# ASM2001.net
KiCad netlist of a schematic drawn in EAGLE
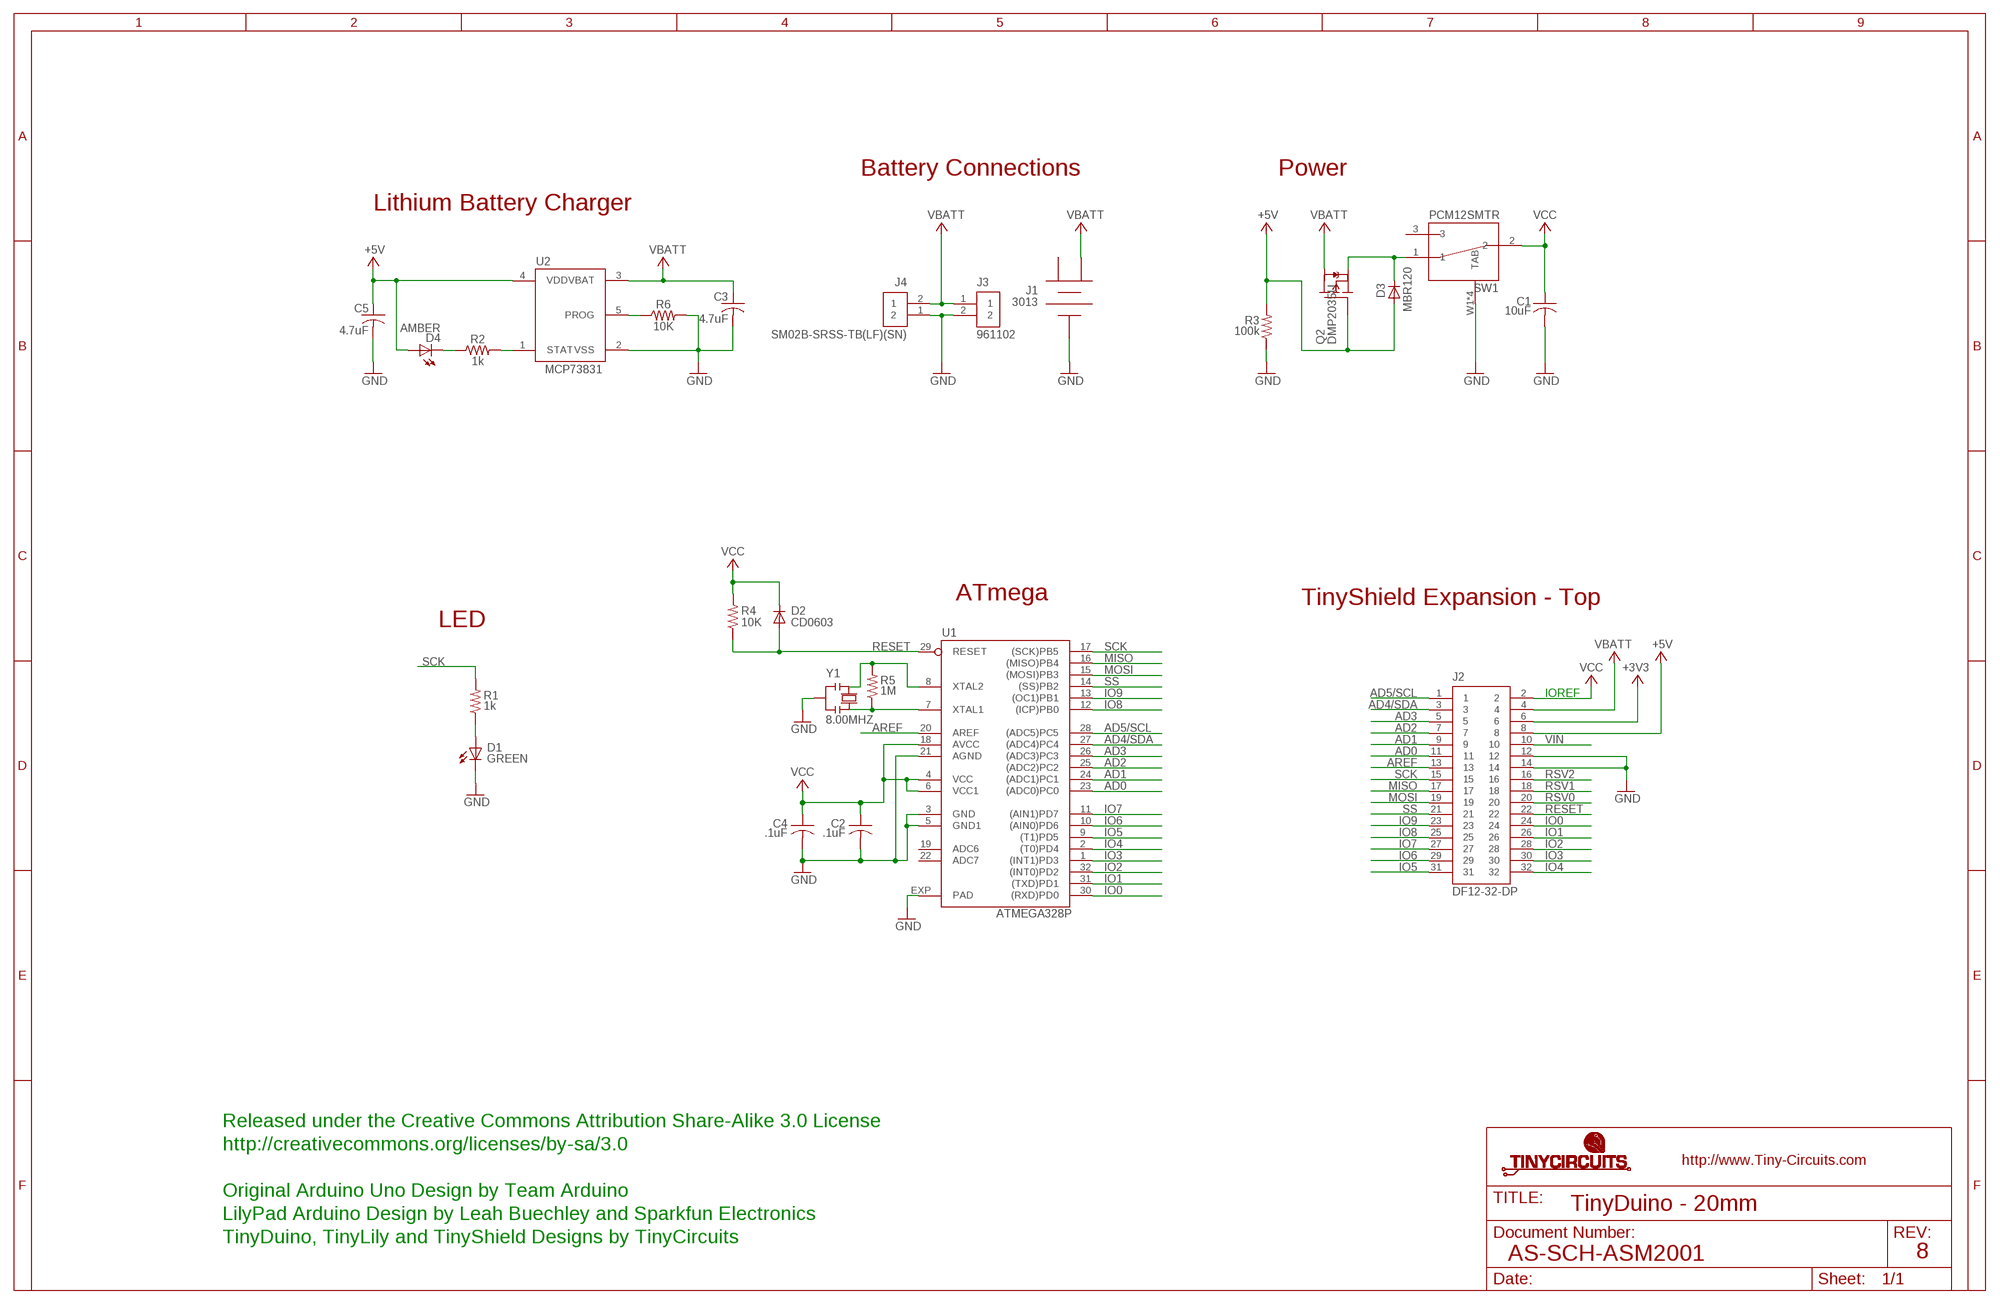
[diagram p0: schematic, sheet 1]

(export (version "E")
  (design (tool "Eeschema 10.0.6"))
  (components
    (comp (ref "C1")
      (value "10uF")
      (footprint "eagle-import:C0603")
      (fields (field (name "PARTNO") "AS-ITM-00002") (field (name "PARTNO_1") "AS-ITM-00002"))
      (libsource (lib "eagle-import") (part "AS-ITM-00002"))
    )
    (comp (ref "C2")
      (value ".1uF")
      (footprint "eagle-import:C0402")
      (fields (field (name "PARTNO") "AS-ITM-00008") (field (name "PARTNO_1") "AS-ITM-00008"))
      (libsource (lib "eagle-import") (part "AS-ITM-00008"))
    )
    (comp (ref "C3")
      (value "4.7uF")
      (footprint "eagle-import:C0402")
      (fields (field (name "PARTNO") "AS-ITM-00242") (field (name "PARTNO_1") "AS-ITM-00242"))
      (libsource (lib "eagle-import") (part "AS-ITM-00242"))
    )
    (comp (ref "C4")
      (value ".1uF")
      (footprint "eagle-import:C0402")
      (fields (field (name "PARTNO") "AS-ITM-00008") (field (name "PARTNO_1") "AS-ITM-00008"))
      (libsource (lib "eagle-import") (part "AS-ITM-00008"))
    )
    (comp (ref "C5")
      (value "4.7uF")
      (footprint "eagle-import:C0402")
      (fields (field (name "PARTNO") "AS-ITM-00242") (field (name "PARTNO_1") "AS-ITM-00242"))
      (libsource (lib "eagle-import") (part "AS-ITM-00242"))
    )
    (comp (ref "D1")
      (value "GREEN")
      (footprint "eagle-import:LNJ_LED")
      (fields (field (name "PARTNO") "AS-ITM-00011") (field (name "PARTNO_1") "AS-ITM-00011"))
      (libsource (lib "eagle-import") (part "AS-ITM-00011"))
    )
    (comp (ref "D2")
      (value "CD0603")
      (footprint "eagle-import:0603")
      (fields (field (name "PARTNO") "AS-ITM-00009") (field (name "PARTNO_1") "AS-ITM-00009"))
      (libsource (lib "eagle-import") (part "AS-ITM-00009"))
    )
    (comp (ref "D3")
      (value "MBR120")
      (footprint "eagle-import:SOD-123FL")
      (fields (field (name "PARTNO") "AS-ITM-00111"))
      (libsource (lib "eagle-import") (part "AS-ITM-00111"))
    )
    (comp (ref "D4")
      (value "AMBER")
      (footprint "eagle-import:LNJ_LED")
      (fields (field (name "PARTNO") "AS-ITM-00026") (field (name "PARTNO_1") "AS-ITM-00026"))
      (libsource (lib "eagle-import") (part "AS-ITM-00026"))
    )
    (comp (ref "J1")
      (value "3013")
      (footprint "eagle-import:3013")
      (fields (field (name "PARTNO") "AS-ITM-00001") (field (name "PARTNO_1") "AS-ITM-00001"))
      (libsource (lib "eagle-import") (part "AS-ITM-00001"))
    )
    (comp (ref "J2")
      (value "DF12-32-DP")
      (footprint "eagle-import:DF12-32-DP")
      (fields (field (name "PARTNO") "AS-ITM-00015") (field (name "PARTNO_1") "AS-ITM-00015"))
      (libsource (lib "eagle-import") (part "AS-ITM-00015"))
    )
    (comp (ref "J3")
      (value "961102")
      (footprint "eagle-import:2X.1_")
      (fields (field (name "PARTNO") "AS-ITM-00044"))
      (libsource (lib "eagle-import") (part "AS-ITM-00044"))
    )
    (comp (ref "J4")
      (value "SM02B-SRSS-TB(LF)(SN)")
      (footprint "eagle-import:JST_SH_2X1")
      (fields (field (name "PARTNO") "AS-ITM-00231"))
      (libsource (lib "eagle-import") (part "AS-ITM-00231"))
    )
    (comp (ref "Q2")
      (value "DMP2035U")
      (footprint "eagle-import:SOT23")
      (fields (field (name "PARTNO") "AS-ITM-00024"))
      (libsource (lib "eagle-import") (part "AS-ITM-00024"))
    )
    (comp (ref "R1")
      (value "1k")
      (footprint "eagle-import:0402")
      (fields (field (name "PARTNO") "AS-ITM-00003") (field (name "PARTNO_1") "AS-ITM-00003"))
      (libsource (lib "eagle-import") (part "AS-ITM-00003"))
    )
    (comp (ref "R2")
      (value "1k")
      (footprint "eagle-import:0402")
      (fields (field (name "PARTNO") "AS-ITM-00003") (field (name "PARTNO_1") "AS-ITM-00003"))
      (libsource (lib "eagle-import") (part "AS-ITM-00003"))
    )
    (comp (ref "R3")
      (value "100k")
      (footprint "eagle-import:0402")
      (fields (field (name "PARTNO") "AS-ITM-00004") (field (name "PARTNO_1") "AS-ITM-00004"))
      (libsource (lib "eagle-import") (part "AS-ITM-00004"))
    )
    (comp (ref "R4")
      (value "10K")
      (footprint "eagle-import:0402")
      (fields (field (name "PARTNO") "AS-ITM-00032") (field (name "PARTNO_1") "AS-ITM-00032"))
      (libsource (lib "eagle-import") (part "AS-ITM-00032"))
    )
    (comp (ref "R5")
      (value "1M")
      (footprint "eagle-import:0402")
      (fields (field (name "PARTNO") "AS-ITM-00005") (field (name "PARTNO_1") "AS-ITM-00005"))
      (libsource (lib "eagle-import") (part "AS-ITM-00005"))
    )
    (comp (ref "R6")
      (value "10K")
      (footprint "eagle-import:0402")
      (fields (field (name "PARTNO") "AS-ITM-00032"))
      (libsource (lib "eagle-import") (part "AS-ITM-00032"))
    )
    (comp (ref "SW1")
      (value "PCM12SMTR")
      (footprint "eagle-import:PCM12SMTR")
      (fields (field (name "PARTNO") "AS-ITM-00220"))
      (libsource (lib "eagle-import") (part "AS-ITM-00220"))
    )
    (comp (ref "U1")
      (value "ATMEGA328P")
      (footprint "eagle-import:ATMEL_QFN32")
      (fields (field (name "PARTNO") "AS-ITM-00013") (field (name "PARTNO_1") "AS-ITM-00013"))
      (libsource (lib "eagle-import") (part "AS-ITM-00013MU"))
    )
    (comp (ref "U2")
      (value "MCP73831")
      (footprint "eagle-import:SOT-23")
      (fields (field (name "PARTNO") "AS-ITM-00136"))
      (libsource (lib "eagle-import") (part "AS-ITM-00136"))
    )
    (comp (ref "Y1")
      (value "8.00MHZ")
      (footprint "eagle-import:RESONATOR_SMALL")
      (fields (field (name "PARTNO") "AS-ITM-0027") (field (name "PARTNO_1") "AS-ITM-00027"))
      (libsource (lib "eagle-import") (part "AS-ITM-00027B"))
    )
  )
  (nets
    (net (code "1") (name "+3V3") (class "Default")
      (node (ref "J2") (pin "6") (pinfunction "6_6") (pintype "bidirectional"))
    )
    (net (code "2") (name "+5V") (class "Default")
      (node (ref "C5") (pin "1") (pinfunction "1_1") (pintype "passive"))
      (node (ref "D3") (pin "A") (pinfunction "A_A") (pintype "passive"))
      (node (ref "D4") (pin "A") (pinfunction "A_A") (pintype "passive"))
      (node (ref "J2") (pin "8") (pinfunction "8_8") (pintype "bidirectional"))
      (node (ref "Q2") (pin "B") (pinfunction "G_B") (pintype "passive"))
      (node (ref "R3") (pin "2") (pinfunction "2_2") (pintype "passive"))
      (node (ref "U2") (pin "4") (pinfunction "VDD_4") (pintype "bidirectional"))
    )
    (net (code "3") (name "/1") (class "Default")
      (node (ref "J1") (pin "1") (pinfunction "1_1") (pintype "power_in"))
    )
    (net (code "4") (name "/AD0") (class "Default")
      (node (ref "J2") (pin "11") (pinfunction "11_11") (pintype "bidirectional"))
      (node (ref "U1") (pin "23") (pinfunction "(ADC0)PC0_23") (pintype "bidirectional"))
    )
    (net (code "5") (name "/AD1") (class "Default")
      (node (ref "J2") (pin "9") (pinfunction "9_9") (pintype "bidirectional"))
      (node (ref "U1") (pin "24") (pinfunction "(ADC1)PC1_24") (pintype "bidirectional"))
    )
    (net (code "6") (name "/AD2") (class "Default")
      (node (ref "J2") (pin "7") (pinfunction "7_7") (pintype "bidirectional"))
      (node (ref "U1") (pin "25") (pinfunction "(ADC2)PC2_25") (pintype "bidirectional"))
    )
    (net (code "7") (name "/AD3") (class "Default")
      (node (ref "J2") (pin "5") (pinfunction "5_5") (pintype "bidirectional"))
      (node (ref "U1") (pin "26") (pinfunction "(ADC3)PC3_26") (pintype "bidirectional"))
    )
    (net (code "8") (name "/AD4{slash}SDA") (class "Default")
      (node (ref "J2") (pin "3") (pinfunction "3_3") (pintype "bidirectional"))
      (node (ref "U1") (pin "27") (pinfunction "(ADC4)PC4_27") (pintype "bidirectional"))
    )
    (net (code "9") (name "/AD5{slash}SCL") (class "Default")
      (node (ref "J2") (pin "1") (pinfunction "1_1") (pintype "bidirectional"))
      (node (ref "U1") (pin "28") (pinfunction "(ADC5)PC5_28") (pintype "bidirectional"))
    )
    (net (code "10") (name "/AREF") (class "Default")
      (node (ref "J2") (pin "13") (pinfunction "13_13") (pintype "bidirectional"))
      (node (ref "U1") (pin "20") (pinfunction "AREF_20") (pintype "passive"))
    )
    (net (code "11") (name "/IO0") (class "Default")
      (node (ref "J2") (pin "24") (pinfunction "24_24") (pintype "bidirectional"))
      (node (ref "U1") (pin "30") (pinfunction "(RXD)PD0_30") (pintype "bidirectional"))
    )
    (net (code "12") (name "/IO1") (class "Default")
      (node (ref "J2") (pin "26") (pinfunction "26_26") (pintype "bidirectional"))
      (node (ref "U1") (pin "31") (pinfunction "(TXD)PD1_31") (pintype "bidirectional"))
    )
    (net (code "13") (name "/IO2") (class "Default")
      (node (ref "J2") (pin "28") (pinfunction "28_28") (pintype "bidirectional"))
      (node (ref "U1") (pin "32") (pinfunction "(INT0)PD2_32") (pintype "bidirectional"))
    )
    (net (code "14") (name "/IO3") (class "Default")
      (node (ref "J2") (pin "30") (pinfunction "30_30") (pintype "bidirectional"))
      (node (ref "U1") (pin "1") (pinfunction "(INT1)PD3_1") (pintype "bidirectional"))
    )
    (net (code "15") (name "/IO4") (class "Default")
      (node (ref "J2") (pin "32") (pinfunction "32_32") (pintype "bidirectional"))
      (node (ref "U1") (pin "2") (pinfunction "(T0)PD4_2") (pintype "bidirectional"))
    )
    (net (code "16") (name "/IO5") (class "Default")
      (node (ref "J2") (pin "31") (pinfunction "31_31") (pintype "bidirectional"))
      (node (ref "U1") (pin "9") (pinfunction "(T1)PD5_9") (pintype "bidirectional"))
    )
    (net (code "17") (name "/IO6") (class "Default")
      (node (ref "J2") (pin "29") (pinfunction "29_29") (pintype "bidirectional"))
      (node (ref "U1") (pin "10") (pinfunction "(AIN0)PD6_10") (pintype "bidirectional"))
    )
    (net (code "18") (name "/IO7") (class "Default")
      (node (ref "J2") (pin "27") (pinfunction "27_27") (pintype "bidirectional"))
      (node (ref "U1") (pin "11") (pinfunction "(AIN1)PD7_11") (pintype "bidirectional"))
    )
    (net (code "19") (name "/IO8") (class "Default")
      (node (ref "J2") (pin "25") (pinfunction "25_25") (pintype "bidirectional"))
      (node (ref "U1") (pin "12") (pinfunction "(ICP)PB0_12") (pintype "bidirectional"))
    )
    (net (code "20") (name "/IO9") (class "Default")
      (node (ref "J2") (pin "23") (pinfunction "23_23") (pintype "bidirectional"))
      (node (ref "U1") (pin "13") (pinfunction "(OC1)PB1_13") (pintype "bidirectional"))
    )
    (net (code "21") (name "/MISO") (class "Default")
      (node (ref "J2") (pin "17") (pinfunction "17_17") (pintype "bidirectional"))
      (node (ref "U1") (pin "16") (pinfunction "(MISO)PB4_16") (pintype "bidirectional"))
    )
    (net (code "22") (name "/MOSI") (class "Default")
      (node (ref "J2") (pin "19") (pinfunction "19_19") (pintype "bidirectional"))
      (node (ref "U1") (pin "15") (pinfunction "(MOSI)PB3_15") (pintype "bidirectional"))
    )
    (net (code "23") (name "/RESET") (class "Default")
      (node (ref "D2") (pin "A") (pinfunction "A_A") (pintype "passive"))
      (node (ref "J2") (pin "22") (pinfunction "22_22") (pintype "bidirectional"))
      (node (ref "R4") (pin "1") (pinfunction "1_1") (pintype "passive"))
      (node (ref "U1") (pin "29") (pinfunction "RESET_29") (pintype "input"))
    )
    (net (code "24") (name "/RSV0") (class "Default")
      (node (ref "J2") (pin "20") (pinfunction "20_20") (pintype "bidirectional"))
    )
    (net (code "25") (name "/RSV1") (class "Default")
      (node (ref "J2") (pin "18") (pinfunction "18_18") (pintype "bidirectional"))
    )
    (net (code "26") (name "/RSV2") (class "Default")
      (node (ref "J2") (pin "16") (pinfunction "16_16") (pintype "bidirectional"))
    )
    (net (code "27") (name "/SCK") (class "Default")
      (node (ref "J2") (pin "15") (pinfunction "15_15") (pintype "bidirectional"))
      (node (ref "R1") (pin "2") (pinfunction "2_2") (pintype "passive"))
      (node (ref "U1") (pin "17") (pinfunction "(SCK)PB5_17") (pintype "bidirectional"))
    )
    (net (code "28") (name "/SS") (class "Default")
      (node (ref "J2") (pin "21") (pinfunction "21_21") (pintype "bidirectional"))
      (node (ref "U1") (pin "14") (pinfunction "(SS)PB2_14") (pintype "bidirectional"))
    )
    (net (code "29") (name "/VIN") (class "Default")
      (node (ref "J2") (pin "10") (pinfunction "10_10") (pintype "bidirectional"))
    )
    (net (code "30") (name "GND") (class "Default")
      (node (ref "C1") (pin "2") (pinfunction "2_2") (pintype "passive"))
      (node (ref "C2") (pin "2") (pinfunction "2_2") (pintype "passive"))
      (node (ref "C3") (pin "2") (pinfunction "2_2") (pintype "passive"))
      (node (ref "C4") (pin "2") (pinfunction "2_2") (pintype "passive"))
      (node (ref "C5") (pin "2") (pinfunction "2_2") (pintype "passive"))
      (node (ref "D1") (pin "C") (pinfunction "C_C") (pintype "passive"))
      (node (ref "J1") (pin "3") (pinfunction "3_3") (pintype "power_in"))
      (node (ref "J2") (pin "12") (pinfunction "12_12") (pintype "bidirectional"))
      (node (ref "J2") (pin "14") (pinfunction "14_14") (pintype "bidirectional"))
      (node (ref "J3") (pin "2") (pinfunction "2_2") (pintype "bidirectional"))
      (node (ref "J4") (pin "1") (pinfunction "2_1") (pintype "bidirectional"))
      (node (ref "R3") (pin "1") (pinfunction "1_1") (pintype "passive"))
      (node (ref "R6") (pin "2") (pinfunction "2_2") (pintype "passive"))
      (node (ref "SW1") (pin "W1") (pinfunction "TAB_W1") (pintype "bidirectional"))
      (node (ref "SW1") (pin "W2") (pinfunction "TAB_W2") (pintype "bidirectional"))
      (node (ref "SW1") (pin "W3") (pinfunction "TAB_W3") (pintype "bidirectional"))
      (node (ref "SW1") (pin "W4") (pinfunction "TAB_W4") (pintype "bidirectional"))
      (node (ref "U1") (pin "21") (pinfunction "AGND_21") (pintype "power_in"))
      (node (ref "U1") (pin "3") (pinfunction "GND_3") (pintype "power_in"))
      (node (ref "U1") (pin "5") (pinfunction "GND1_5") (pintype "power_in"))
      (node (ref "U1") (pin "EXP") (pinfunction "PAD_EXP") (pintype "power_in"))
      (node (ref "U2") (pin "2") (pinfunction "VSS_2") (pintype "bidirectional"))
      (node (ref "Y1") (pin "2") (pinfunction "2_2") (pintype "passive"))
    )
    (net (code "31") (name "Net-(D1-PadA)") (class "Default")
      (node (ref "D1") (pin "A") (pinfunction "A_A") (pintype "passive"))
      (node (ref "R1") (pin "1") (pinfunction "1_1") (pintype "passive"))
    )
    (net (code "32") (name "Net-(D4-PadC)") (class "Default")
      (node (ref "D4") (pin "C") (pinfunction "C_C") (pintype "passive"))
      (node (ref "R2") (pin "1") (pinfunction "1_1") (pintype "passive"))
    )
    (net (code "33") (name "Net-(Q2-S)") (class "Default")
      (node (ref "D3") (pin "C") (pinfunction "C_C") (pintype "passive"))
      (node (ref "Q2") (pin "E") (pinfunction "S_E") (pintype "passive"))
      (node (ref "SW1") (pin "1") (pinfunction "1_1") (pintype "bidirectional"))
    )
    (net (code "34") (name "Net-(U1-XTAL1)") (class "Default")
      (node (ref "R5") (pin "1") (pinfunction "1_1") (pintype "passive"))
      (node (ref "U1") (pin "7") (pinfunction "XTAL1_7") (pintype "bidirectional"))
      (node (ref "Y1") (pin "3") (pinfunction "3_3") (pintype "passive"))
    )
    (net (code "35") (name "Net-(U1-XTAL2)") (class "Default")
      (node (ref "R5") (pin "2") (pinfunction "2_2") (pintype "passive"))
      (node (ref "U1") (pin "8") (pinfunction "XTAL2_8") (pintype "bidirectional"))
      (node (ref "Y1") (pin "1") (pinfunction "1_1") (pintype "passive"))
    )
    (net (code "36") (name "Net-(U2-PROG)") (class "Default")
      (node (ref "R6") (pin "1") (pinfunction "1_1") (pintype "passive"))
      (node (ref "U2") (pin "5") (pinfunction "PROG_5") (pintype "bidirectional"))
    )
    (net (code "37") (name "Net-(U2-STAT)") (class "Default")
      (node (ref "R2") (pin "2") (pinfunction "2_2") (pintype "passive"))
      (node (ref "U2") (pin "1") (pinfunction "STAT_1") (pintype "bidirectional"))
    )
    (net (code "38") (name "VBATT") (class "Default")
      (node (ref "C3") (pin "1") (pinfunction "1_1") (pintype "passive"))
      (node (ref "J1") (pin "2") (pinfunction "2_2") (pintype "power_in"))
      (node (ref "J2") (pin "4") (pinfunction "4_4") (pintype "bidirectional"))
      (node (ref "J3") (pin "1") (pinfunction "1_1") (pintype "bidirectional"))
      (node (ref "J4") (pin "2") (pinfunction "1_2") (pintype "bidirectional"))
      (node (ref "Q2") (pin "C") (pinfunction "D_C") (pintype "passive"))
      (node (ref "U2") (pin "3") (pinfunction "VBAT_3") (pintype "bidirectional"))
    )
    (net (code "39") (name "VCC") (class "Default")
      (node (ref "C1") (pin "1") (pinfunction "1_1") (pintype "passive"))
      (node (ref "C2") (pin "1") (pinfunction "1_1") (pintype "passive"))
      (node (ref "C4") (pin "1") (pinfunction "1_1") (pintype "passive"))
      (node (ref "D2") (pin "C") (pinfunction "C_C") (pintype "passive"))
      (node (ref "J2") (pin "2") (pinfunction "2_2") (pintype "bidirectional"))
      (node (ref "R4") (pin "2") (pinfunction "2_2") (pintype "passive"))
      (node (ref "SW1") (pin "2") (pinfunction "2_2") (pintype "bidirectional"))
      (node (ref "U1") (pin "18") (pinfunction "AVCC_18") (pintype "power_in"))
      (node (ref "U1") (pin "4") (pinfunction "VCC_4") (pintype "power_in"))
      (node (ref "U1") (pin "6") (pinfunction "VCC1_6") (pintype "power_in"))
    )
    (net (code "40") (name "unconnected-(SW1-Pad3)") (class "Default")
      (node (ref "SW1") (pin "3") (pinfunction "3_3") (pintype "bidirectional"))
    )
    (net (code "41") (name "unconnected-(U1-ADC6-Pad19)") (class "Default")
      (node (ref "U1") (pin "19") (pinfunction "ADC6_19") (pintype "bidirectional"))
    )
    (net (code "42") (name "unconnected-(U1-ADC7-Pad22)") (class "Default")
      (node (ref "U1") (pin "22") (pinfunction "ADC7_22") (pintype "bidirectional"))
    )
  )
)
